# nfc-epd-power.net
KiCad netlist of a schematic drawn in Altium Designer
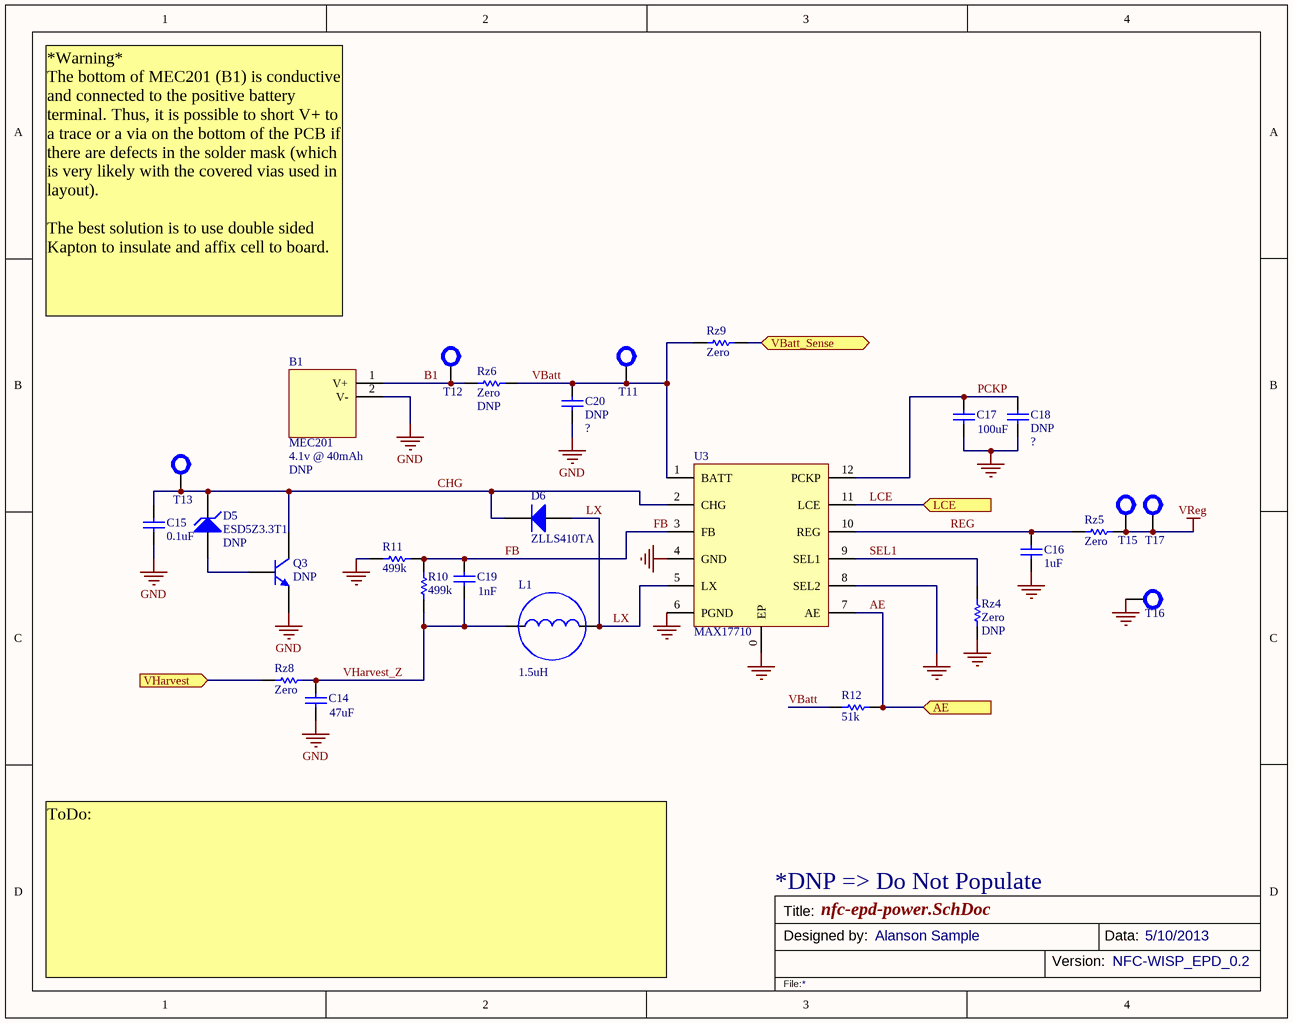
[diagram p0: nfc-epd-power.SchDoc]

(export (version "E")
  (design (tool "Eeschema 10.0.6"))
  (components
    (comp (ref "B1")
      (value "MEC201")
      (footprint "Battery - MEC201 - Caution")
      (description "ThinFilm solid state battery  - 4.1V 1.0MAH")
      (fields
        (field (name "MANUFACTURER PART NUMBER") "MEC201-10S (several in same formfactor)")
        (field (name "MANUFACTURER") "Infinite Power Solutions")
        (field (name "NOTE") "DNP")
        (field (name "ALTIUM_VALUE") "4.1v @ 40mAh")
      )
      (libsource (lib "WISP_AD10") (part "Battery - MEC201"))
    )
    (comp (ref "C14")
      (value "47uF")
      (footprint "0805")
      (description "Ceramic Capacitor (Surface Mount)")
      (fields (field (name "MANUFACTURER") "Generic Ceramic Chip Cap (TBD)") (field (name "Comment") "Cap"))
      (libsource (lib "WREL_AD10") (part "Cap"))
    )
    (comp (ref "C15")
      (value "0.1uF")
      (footprint "0603")
      (description "Ceramic Capacitor (Surface Mount)")
      (fields (field (name "MANUFACTURER") "Generic Ceramic Chip Cap (TBD)") (field (name "Comment") "Cap"))
      (libsource (lib "WISP_AD10") (part "Cap"))
    )
    (comp (ref "C16")
      (value "1uF")
      (footprint "0603")
      (description "Ceramic Capacitor (Surface Mount)")
      (fields (field (name "MANUFACTURER") "Generic Ceramic Chip Cap (TBD)") (field (name "Comment") "Cap"))
      (libsource (lib "WREL_AD10") (part "Cap"))
    )
    (comp (ref "C17")
      (value "100uF")
      (footprint "1206")
      (description "Ceramic Capacitor (Surface Mount)")
      (fields (field (name "MANUFACTURER") "Generic Ceramic Chip Cap (TBD)") (field (name "Comment") "Cap"))
      (libsource (lib "WREL_AD10") (part "Cap"))
    )
    (comp (ref "C18")
      (value "?")
      (footprint "1206")
      (description "Ceramic Capacitor (Surface Mount)")
      (fields
        (field (name "MANUFACTURER") "Generic Ceramic Chip Cap (TBD)")
        (field (name "NOTE") "DNP")
        (field (name "Comment") "Cap")
      )
      (libsource (lib "WREL_AD10") (part "Cap"))
    )
    (comp (ref "C19")
      (value "1nF")
      (footprint "0603")
      (description "Ceramic Capacitor (Surface Mount)")
      (fields (field (name "MANUFACTURER") "Generic Ceramic Chip Cap (TBD)") (field (name "Comment") "Cap"))
      (libsource (lib "WREL_AD10") (part "Cap"))
    )
    (comp (ref "C20")
      (value "?")
      (footprint "1206")
      (description "Ceramic Capacitor (Surface Mount)")
      (fields
        (field (name "MANUFACTURER") "Generic Ceramic Chip Cap (TBD)")
        (field (name "NOTE") "DNP")
        (field (name "Comment") "Cap")
      )
      (libsource (lib "WREL_AD10") (part "Cap"))
    )
    (comp (ref "D5")
      (value "ESD5Z3.3T1")
      (footprint "SOD-523")
      (description "5V Overvoltage Protection Zener")
      (fields
        (field (name "MANUFACTURER PART NUMBER") "ESD5Z3.3T1G")
        (field (name "MANUFACTURER") "ON Semiconductor")
        (field (name "NOTE") "DNP")
      )
      (libsource (lib "WISP_AD10") (part "ESD5Z3.3T1"))
    )
    (comp (ref "D6")
      (value "ZLLS410TA")
      (footprint "SOD-323")
      (description "General Purpose Diode")
      (fields (field (name "MANUFACTURER") "Diodes Inc") (field (name "DIGI-KEY PART NUMBER") "ZLLS410CT-ND"))
      (libsource (lib "WISP_AD10") (part "Diode"))
    )
    (comp (ref "L1")
      (value "1.5uH")
      (footprint "Inductor - 1008")
      (description "Power Inductor")
      (fields
        (field (name "DIGI-KEY PART NUMBER") "490-5113-2-ND")
        (field (name "MANUFACTURER") "Murata Electronics North America")
      )
      (libsource (lib "EnergyHarvester_2012") (part "Ind - Power"))
    )
    (comp (ref "Q3")
      (value "BJT - Generic")
      (footprint "SOT-323 / SC-70")
      (description "Generic BJT")
      (fields (field (name "NOTE") "DNP"))
      (libsource (lib "WISP_AD10") (part "BJT - Generic"))
    )
    (comp (ref "R10")
      (value "499k")
      (footprint "0603")
      (description "Chip Resistor (Surface Mount)")
      (fields (field (name "MANUFACTURER") "Generic Chip Res (TBD)") (field (name "Comment") "Res"))
      (libsource (lib "WISP_AD10") (part "Res"))
    )
    (comp (ref "R11")
      (value "499k")
      (footprint "0603")
      (description "Chip Resistor (Surface Mount)")
      (fields (field (name "MANUFACTURER") "Generic Chip Res (TBD)") (field (name "Comment") "Res"))
      (libsource (lib "WISP_AD10") (part "Res"))
    )
    (comp (ref "R12")
      (value "51k")
      (footprint "0603")
      (description "Chip Resistor (Surface Mount)")
      (fields (field (name "MANUFACTURER") "Generic Chip Res (TBD)") (field (name "Comment") "Res"))
      (libsource (lib "WREL_AD10") (part "Res"))
    )
    (comp (ref "Rz4")
      (value "Zero")
      (footprint "0603")
      (description "Chip Resistor (Surface Mount)")
      (fields
        (field (name "MANUFACTURER") "Generic Chip Res (TBD)")
        (field (name "NOTE") "DNP")
        (field (name "Comment") "Res")
      )
      (libsource (lib "WREL_AD10") (part "Res"))
    )
    (comp (ref "Rz5")
      (value "Zero")
      (footprint "0603")
      (description "Chip Resistor (Surface Mount)")
      (fields (field (name "MANUFACTURER") "Generic Chip Res (TBD)") (field (name "Comment") "Res"))
      (libsource (lib "WREL_AD10") (part "Res"))
    )
    (comp (ref "Rz6")
      (value "Zero")
      (footprint "0603")
      (description "Chip Resistor (Surface Mount)")
      (fields
        (field (name "MANUFACTURER") "Generic Chip Res (TBD)")
        (field (name "NOTE") "DNP")
        (field (name "Comment") "Res")
      )
      (libsource (lib "WREL_AD10") (part "Res"))
    )
    (comp (ref "Rz8")
      (value "Zero")
      (footprint "0603")
      (description "Chip Resistor (Surface Mount)")
      (fields (field (name "MANUFACTURER") "Generic Chip Res (TBD)") (field (name "Comment") "Res"))
      (libsource (lib "WREL_AD10") (part "Res"))
    )
    (comp (ref "Rz9")
      (value "Zero")
      (footprint "0603")
      (description "Chip Resistor (Surface Mount)")
      (fields (field (name "MANUFACTURER") "Generic Chip Res (TBD)") (field (name "Comment") "Res"))
      (libsource (lib "WREL_AD10") (part "Res"))
    )
    (comp (ref "T11")
      (value "Test Point")
      (footprint "Test Point - Super Small")
      (description "Test Point, large or small foot prints")
      (fields
        (field (name "DIGI-KEY PART NUMBER") "Example: 5000K-ND, 5012K-ND, Surface mount 5015KCT-ND")
        (field (name "MANUFACTURER PART NUMBER") "Example: 5000, 5013")
      )
      (libsource (lib "WISP_AD10") (part "Test Point"))
    )
    (comp (ref "T12")
      (value "Test Point")
      (footprint "Test Point - Super Small")
      (description "Test Point, large or small foot prints")
      (fields
        (field (name "DIGI-KEY PART NUMBER") "Example: 5000K-ND, 5012K-ND, Surface mount 5015KCT-ND")
        (field (name "MANUFACTURER PART NUMBER") "Example: 5000, 5013")
      )
      (libsource (lib "WISP_AD10") (part "Test Point"))
    )
    (comp (ref "T13")
      (value "Test Point")
      (footprint "Test Point - Super Small")
      (description "Test Point, large or small foot prints")
      (fields
        (field (name "DIGI-KEY PART NUMBER") "Example: 5000K-ND, 5012K-ND, Surface mount 5015KCT-ND")
        (field (name "MANUFACTURER PART NUMBER") "Example: 5000, 5013")
      )
      (libsource (lib "WISP_AD10") (part "Test Point"))
    )
    (comp (ref "T15")
      (value "Test Point")
      (footprint "Test Point - Small")
      (description "Test Point, large or small foot prints")
      (fields
        (field (name "MANUFACTURER PART NUMBER") "Example: 5000, 5013")
        (field (name "MANUFACTURER") "Keystone Electronics")
      )
      (libsource (lib "WISP_AD10") (part "Test Point"))
    )
    (comp (ref "T16")
      (value "Test Point")
      (footprint "Test Point - Small")
      (description "Test Point, large or small foot prints")
      (fields
        (field (name "MANUFACTURER PART NUMBER") "Example: 5000, 5013")
        (field (name "MANUFACTURER") "Keystone Electronics")
      )
      (libsource (lib "WISP_AD10") (part "Test Point"))
    )
    (comp (ref "T17")
      (value "Test Point")
      (footprint "Test Point - Small")
      (description "Test Point, large or small foot prints")
      (fields
        (field (name "MANUFACTURER PART NUMBER") "Example: 5000, 5013")
        (field (name "MANUFACTURER") "Keystone Electronics")
      )
      (libsource (lib "WISP_AD10") (part "Test Point"))
    )
    (comp (ref "U3")
      (value "MAX17710")
      (footprint "MAX17710 - Wings")
      (description "IC ENERGY HARVEST MNGR 12UTDFN")
      (fields
        (field (name "MANUFACTURER") "Maxim Integrated")
        (field (name "MANUFACTURER PART NUMBER") "MAX17710G+T")
      )
      (libsource (lib "WISP_AD10") (part "MAX17710"))
    )
  )
  (nets
    (net (code "1") (name "/AE") (class "Default")
      (node (ref "R12") (pin "2") (pinfunction "2_2") (pintype "passive"))
      (node (ref "U3") (pin "7") (pinfunction "AE_7") (pintype "passive"))
    )
    (net (code "2") (name "/B1") (class "Default")
      (node (ref "B1") (pin "1") (pinfunction "V+_1") (pintype "passive"))
      (node (ref "Rz6") (pin "2") (pinfunction "2_2") (pintype "passive"))
      (node (ref "T12") (pin "0") (pinfunction "0_0") (pintype "passive"))
    )
    (net (code "3") (name "/CHG") (class "Default")
      (node (ref "C15") (pin "1") (pinfunction "1_1") (pintype "passive"))
      (node (ref "D5") (pin "1") (pinfunction "C_1") (pintype "passive"))
      (node (ref "D6") (pin "2") (pinfunction "C_2") (pintype "passive"))
      (node (ref "Q3") (pin "3") (pinfunction "C_3") (pintype "passive"))
      (node (ref "T13") (pin "0") (pinfunction "0_0") (pintype "passive"))
      (node (ref "U3") (pin "2") (pinfunction "CHG_2") (pintype "passive"))
    )
    (net (code "4") (name "/FB") (class "Default")
      (node (ref "C19") (pin "2") (pinfunction "2_2") (pintype "passive"))
      (node (ref "R10") (pin "2") (pinfunction "2_2") (pintype "passive"))
      (node (ref "R11") (pin "1") (pinfunction "1_1") (pintype "passive"))
      (node (ref "U3") (pin "3") (pinfunction "FB_3") (pintype "passive"))
    )
    (net (code "5") (name "/LCE") (class "Default")
      (node (ref "U3") (pin "11") (pinfunction "LCE_11") (pintype "passive"))
    )
    (net (code "6") (name "/LX") (class "Default")
      (node (ref "D6") (pin "1") (pinfunction "A_1") (pintype "passive"))
      (node (ref "L1") (pin "2") (pinfunction "2_2") (pintype "passive"))
      (node (ref "U3") (pin "5") (pinfunction "LX_5") (pintype "passive"))
    )
    (net (code "7") (name "/PCKP") (class "Default")
      (node (ref "C17") (pin "2") (pinfunction "2_2") (pintype "passive"))
      (node (ref "C18") (pin "2") (pinfunction "2_2") (pintype "passive"))
      (node (ref "U3") (pin "12") (pinfunction "PCKP_12") (pintype "passive"))
    )
    (net (code "8") (name "/REG") (class "Default")
      (node (ref "C16") (pin "1") (pinfunction "1_1") (pintype "passive"))
      (node (ref "Rz5") (pin "1") (pinfunction "1_1") (pintype "passive"))
      (node (ref "U3") (pin "10") (pinfunction "REG_10") (pintype "passive"))
    )
    (net (code "9") (name "/SEL1") (class "Default")
      (node (ref "Rz4") (pin "1") (pinfunction "1_1") (pintype "passive"))
      (node (ref "U3") (pin "9") (pinfunction "SEL1_9") (pintype "passive"))
    )
    (net (code "10") (name "/VBatt") (class "Default")
      (node (ref "C20") (pin "1") (pinfunction "1_1") (pintype "passive"))
      (node (ref "R12") (pin "1") (pinfunction "1_1") (pintype "passive"))
      (node (ref "Rz6") (pin "1") (pinfunction "1_1") (pintype "passive"))
      (node (ref "Rz9") (pin "1") (pinfunction "1_1") (pintype "passive"))
      (node (ref "T11") (pin "0") (pinfunction "0_0") (pintype "passive"))
      (node (ref "U3") (pin "1") (pinfunction "BATT_1") (pintype "passive"))
    )
    (net (code "11") (name "/VBatt_Sense") (class "Default")
      (node (ref "Rz9") (pin "2") (pinfunction "2_2") (pintype "passive"))
    )
    (net (code "12") (name "/VHarvest") (class "Default")
      (node (ref "Rz8") (pin "1") (pinfunction "1_1") (pintype "passive"))
    )
    (net (code "13") (name "/VHarvest_Z") (class "Default")
      (node (ref "C14") (pin "2") (pinfunction "2_2") (pintype "passive"))
      (node (ref "C19") (pin "1") (pinfunction "1_1") (pintype "passive"))
      (node (ref "L1") (pin "1") (pinfunction "1_1") (pintype "passive"))
      (node (ref "R10") (pin "1") (pinfunction "1_1") (pintype "passive"))
      (node (ref "Rz8") (pin "2") (pinfunction "2_2") (pintype "passive"))
    )
    (net (code "14") (name "GND") (class "Default")
      (node (ref "B1") (pin "2") (pinfunction "V-_2") (pintype "passive"))
      (node (ref "C14") (pin "1") (pinfunction "1_1") (pintype "passive"))
      (node (ref "C15") (pin "2") (pinfunction "2_2") (pintype "passive"))
      (node (ref "C16") (pin "2") (pinfunction "2_2") (pintype "passive"))
      (node (ref "C17") (pin "1") (pinfunction "1_1") (pintype "passive"))
      (node (ref "C18") (pin "1") (pinfunction "1_1") (pintype "passive"))
      (node (ref "C20") (pin "2") (pinfunction "2_2") (pintype "passive"))
      (node (ref "Q3") (pin "2") (pinfunction "E_2") (pintype "passive"))
      (node (ref "R11") (pin "2") (pinfunction "2_2") (pintype "passive"))
      (node (ref "Rz4") (pin "2") (pinfunction "2_2") (pintype "passive"))
      (node (ref "T16") (pin "0") (pinfunction "0_0") (pintype "passive"))
      (node (ref "U3") (pin "0") (pinfunction "EP_0") (pintype "passive"))
      (node (ref "U3") (pin "4") (pinfunction "GND_4") (pintype "passive"))
      (node (ref "U3") (pin "6") (pinfunction "PGND_6") (pintype "passive"))
      (node (ref "U3") (pin "8") (pinfunction "SEL2_8") (pintype "passive"))
    )
    (net (code "15") (name "Net-(D5-A)") (class "Default")
      (node (ref "D5") (pin "2") (pinfunction "A_2") (pintype "passive"))
      (node (ref "Q3") (pin "1") (pinfunction "B_1") (pintype "passive"))
    )
    (net (code "16") (name "VReg") (class "Default")
      (node (ref "Rz5") (pin "2") (pinfunction "2_2") (pintype "passive"))
      (node (ref "T15") (pin "0") (pinfunction "0_0") (pintype "passive"))
      (node (ref "T17") (pin "0") (pinfunction "0_0") (pintype "passive"))
    )
  )
)
